# eMMC_QSPI.net
KiCad netlist of a schematic drawn in Altium Designer
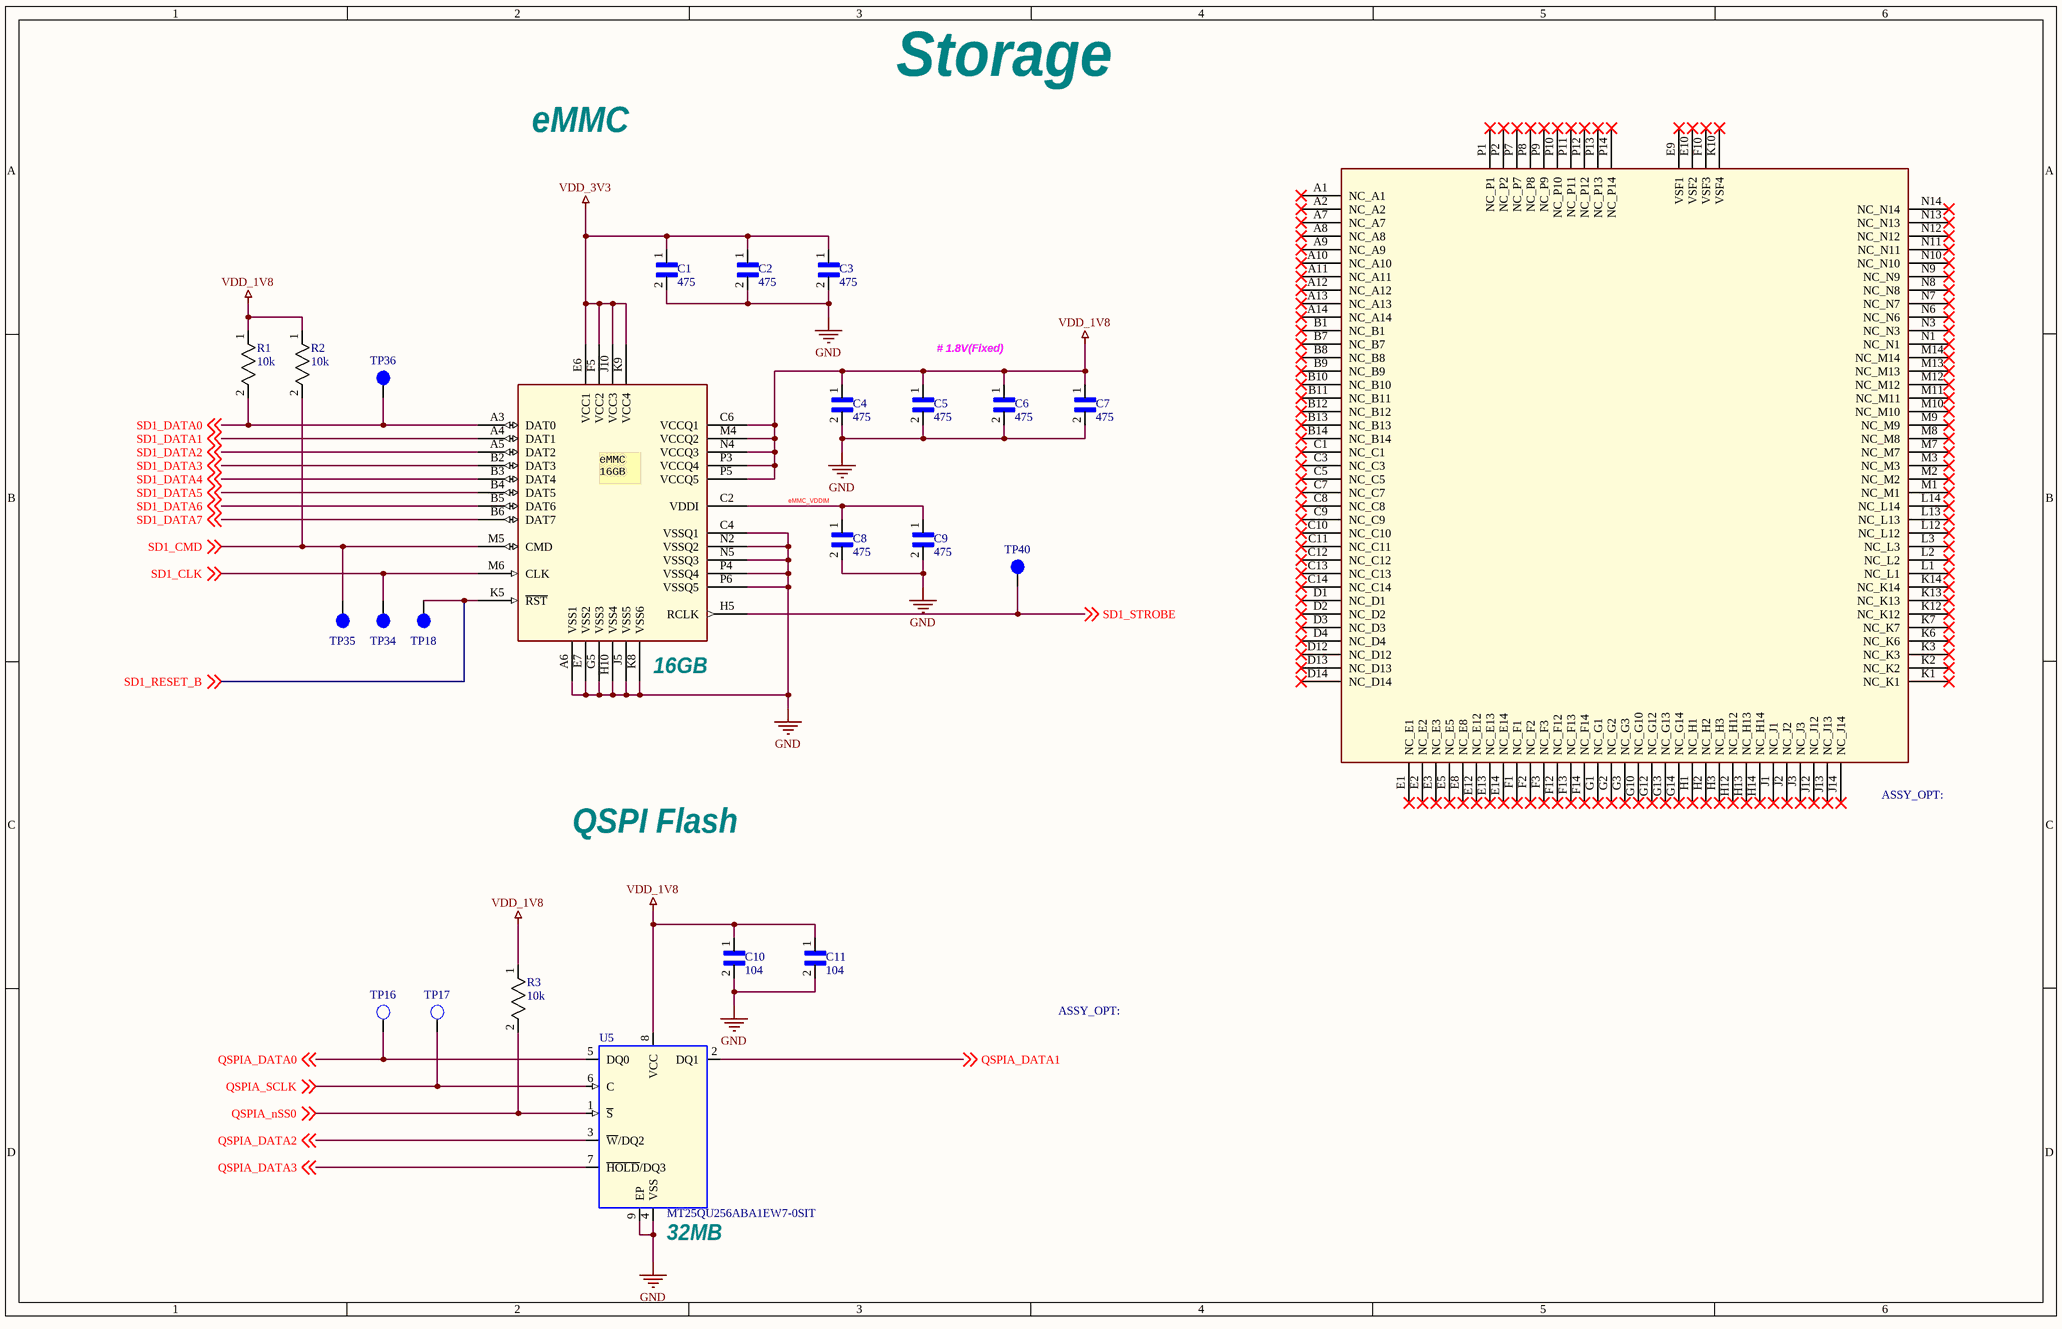
[diagram p0: eMMC_QSPI.SchDoc]

(export (version "E")
  (design (tool "Eeschema 10.0.6"))
  (components
    (comp (ref "C1")
      (value "475")
      (footprint "CAPC1005X55N2")
      (description "Multilayer Ceramic Capacitor, 4.7 uF, 50 V, ï¿½ 10%, X5R, 0402 [1005 Metric]")
      (fields
        (field (name "MANUFACTURER") "Yageo")
        (field (name "MANUFACTURER PART NUMBER") "CC0402MRX5R6BB475")
      )
      (libsource (lib "imx8mnano") (part "CC0402MRX5R6BB475"))
    )
    (comp (ref "C2")
      (value "475")
      (footprint "CAPC1005X55N2")
      (description "Multilayer Ceramic Capacitor, 4.7 uF, 50 V, ï¿½ 10%, X5R, 0402 [1005 Metric]")
      (fields
        (field (name "MANUFACTURER") "Yageo")
        (field (name "MANUFACTURER PART NUMBER") "CC0402MRX5R6BB475")
      )
      (libsource (lib "imx8mnano") (part "CC0402MRX5R6BB475"))
    )
    (comp (ref "C3")
      (value "475")
      (footprint "CAPC1005X55N2")
      (description "Multilayer Ceramic Capacitor, 4.7 uF, 50 V, ï¿½ 10%, X5R, 0402 [1005 Metric]")
      (fields
        (field (name "MANUFACTURER") "Yageo")
        (field (name "MANUFACTURER PART NUMBER") "CC0402MRX5R6BB475")
      )
      (libsource (lib "imx8mnano") (part "CC0402MRX5R6BB475"))
    )
    (comp (ref "C4")
      (value "475")
      (footprint "CAPC1005X55N2")
      (description "Multilayer Ceramic Capacitor, 4.7 uF, 50 V, ï¿½ 10%, X5R, 0402 [1005 Metric]")
      (fields
        (field (name "MANUFACTURER") "Yageo")
        (field (name "MANUFACTURER PART NUMBER") "CC0402MRX5R6BB475")
      )
      (libsource (lib "imx8mnano") (part "CC0402MRX5R6BB475"))
    )
    (comp (ref "C5")
      (value "475")
      (footprint "CAPC1005X55N2")
      (description "Multilayer Ceramic Capacitor, 4.7 uF, 50 V, ï¿½ 10%, X5R, 0402 [1005 Metric]")
      (fields
        (field (name "MANUFACTURER") "Yageo")
        (field (name "MANUFACTURER PART NUMBER") "CC0402MRX5R6BB475")
      )
      (libsource (lib "imx8mnano") (part "CC0402MRX5R6BB475"))
    )
    (comp (ref "C6")
      (value "475")
      (footprint "CAPC1005X55N2")
      (description "Multilayer Ceramic Capacitor, 4.7 uF, 50 V, ï¿½ 10%, X5R, 0402 [1005 Metric]")
      (fields
        (field (name "MANUFACTURER") "Yageo")
        (field (name "MANUFACTURER PART NUMBER") "CC0402MRX5R6BB475")
      )
      (libsource (lib "imx8mnano") (part "CC0402MRX5R6BB475"))
    )
    (comp (ref "C7")
      (value "475")
      (footprint "CAPC1005X55N2")
      (description "Multilayer Ceramic Capacitor, 4.7 uF, 50 V, ï¿½ 10%, X5R, 0402 [1005 Metric]")
      (fields
        (field (name "MANUFACTURER") "Yageo")
        (field (name "MANUFACTURER PART NUMBER") "CC0402MRX5R6BB475")
      )
      (libsource (lib "imx8mnano") (part "CC0402MRX5R6BB475"))
    )
    (comp (ref "C8")
      (value "475")
      (footprint "CAPC1005X55N2")
      (description "Multilayer Ceramic Capacitor, 4.7 uF, 50 V, ï¿½ 10%, X5R, 0402 [1005 Metric]")
      (fields
        (field (name "MANUFACTURER") "Yageo")
        (field (name "MANUFACTURER PART NUMBER") "CC0402MRX5R6BB475")
      )
      (libsource (lib "imx8mnano") (part "CC0402MRX5R6BB475"))
    )
    (comp (ref "C9")
      (value "475")
      (footprint "CAPC1005X55N2")
      (description "Multilayer Ceramic Capacitor, 4.7 uF, 50 V, ï¿½ 10%, X5R, 0402 [1005 Metric]")
      (fields
        (field (name "MANUFACTURER") "Yageo")
        (field (name "MANUFACTURER PART NUMBER") "CC0402MRX5R6BB475")
      )
      (libsource (lib "imx8mnano") (part "CC0402MRX5R6BB475"))
    )
    (comp (ref "C10")
      (value "104")
      (footprint "CAPC1005X55N2")
      (description "Multilayer Ceramic Capacitor, 0.1 uF, 16 V, ï¿½ 10%, X7R, 0402 [1005 Metric]")
      (fields
        (field (name "MANUFACTURER") "Yageo")
        (field (name "MANUFACTURER PART NUMBER") "CC0402KRX7R7BB104")
      )
      (libsource (lib "imx8mnano") (part "CC0402KRX7R7BB104"))
    )
    (comp (ref "C11")
      (value "104")
      (footprint "CAPC1005X55N2")
      (description "Multilayer Ceramic Capacitor, 0.1 uF, 16 V, ï¿½ 10%, X7R, 0402 [1005 Metric]")
      (fields
        (field (name "MANUFACTURER") "Yageo")
        (field (name "MANUFACTURER PART NUMBER") "CC0402KRX7R7BB104")
      )
      (libsource (lib "imx8mnano") (part "CC0402KRX7R7BB104"))
    )
    (comp (ref "R1")
      (value "10k")
      (footprint "RC0402X")
      (description "SMD Chip Resistor, 10 kOhm, ï¿½ 5%, 62.5 mW, 0402 [1005 Metric], Thick Film, General Purpose")
      (fields
        (field (name "MANUFACTURER") "Yageo")
        (field (name "MANUFACTURER PART NUMBER") "RC0402JR-0710KL")
      )
      (libsource (lib "imx8mnano") (part "RC0402JR-0710KL"))
    )
    (comp (ref "R2")
      (value "10k")
      (footprint "RC0402X")
      (description "SMD Chip Resistor, 10 kOhm, ï¿½ 5%, 62.5 mW, 0402 [1005 Metric], Thick Film, General Purpose")
      (fields
        (field (name "MANUFACTURER") "Yageo")
        (field (name "MANUFACTURER PART NUMBER") "RC0402JR-0710KL")
      )
      (libsource (lib "imx8mnano") (part "RC0402JR-0710KL"))
    )
    (comp (ref "R3")
      (value "10k")
      (footprint "RC0402X")
      (description "SMD Chip Resistor, 10 kOhm, ï¿½ 5%, 62.5 mW, 0402 [1005 Metric], Thick Film, General Purpose")
      (fields
        (field (name "MANUFACTURER") "Yageo")
        (field (name "MANUFACTURER PART NUMBER") "RC0402JR-0710KL")
      )
      (libsource (lib "imx8mnano") (part "RC0402JR-0710KL"))
    )
    (comp (ref "TP16")
      (value "TP_35MIL")
      (footprint "testpoint_35mil")
      (description "TEST POINT PAD .035 SMT, no part to order")
      (libsource (lib "*") (part "T POINT R"))
    )
    (comp (ref "TP17")
      (value "TP_35MIL")
      (footprint "testpoint_35mil")
      (description "TEST POINT PAD .035 SMT, no part to order")
      (libsource (lib "*") (part "T POINT R"))
    )
    (comp (ref "TP18")
      (value "tpad_020")
      (footprint "tpad_020")
      (description "TEST POINT PAD 0.5MM DIA SMT, NO PART TO ORDER")
      (libsource (lib "*") (part "TESTLOOP"))
    )
    (comp (ref "TP34")
      (value "tpad_020")
      (footprint "tpad_020")
      (description "TEST POINT PAD 0.5MM DIA SMT, NO PART TO ORDER")
      (libsource (lib "*") (part "TESTLOOP"))
    )
    (comp (ref "TP35")
      (value "TPAD_015")
      (footprint "TPAD_015")
      (description "TEST POINT PAD 15MIL DIA SMT, NO PART TO ORDER")
      (libsource (lib "*") (part "TESTLOOP"))
    )
    (comp (ref "TP36")
      (value "tpad_020")
      (footprint "tpad_020")
      (description "TEST POINT PAD 0.5MM DIA SMT, NO PART TO ORDER")
      (libsource (lib "*") (part "TESTLOOP"))
    )
    (comp (ref "TP40")
      (value "TPAD_015")
      (footprint "TPAD_015")
      (description "TEST POINT PAD 15MIL DIA SMT, NO PART TO ORDER")
      (libsource (lib "*") (part "TESTLOOP"))
    )
    (comp (ref "U1")
      (value "SDINBDG4-16G_VFBGA_153P")
      (footprint "BGA153N50P14X14_1300X1150X80")
      (libsource (lib "imx8mnano") (part "SDINBDG4-16G_VFBGA_153P"))
    )
    (comp (ref "U5")
      (value "MT25QU256ABA1EW7-0SIT")
      (footprint "dfn8_1p27_6x5mm_3p1")
      (description "IC MEM FLASH SERIAL NOR 256MBIT 166MHZ 1.7-2V WPDFN8")
      (fields (field (name "VOLTAGE") "1.7-2V"))
      (libsource (lib "*") (part "MT25QL256ABA1EW9_9P"))
    )
  )
  (nets
    (net (code "1") (name "/eMMC_VDDIM") (class "Default")
      (node (ref "C8") (pin "1") (pinfunction "1_1") (pintype "passive"))
      (node (ref "C9") (pin "1") (pinfunction "1_1") (pintype "passive"))
      (node (ref "U1") (pin "C2") (pinfunction "VDDI_C2") (pintype "power_in"))
    )
    (net (code "2") (name "GND") (class "Default")
      (node (ref "C1") (pin "2") (pinfunction "2_2") (pintype "passive"))
      (node (ref "C10") (pin "2") (pinfunction "2_2") (pintype "passive"))
      (node (ref "C11") (pin "2") (pinfunction "2_2") (pintype "passive"))
      (node (ref "C2") (pin "2") (pinfunction "2_2") (pintype "passive"))
      (node (ref "C3") (pin "2") (pinfunction "2_2") (pintype "passive"))
      (node (ref "C4") (pin "2") (pinfunction "2_2") (pintype "passive"))
      (node (ref "C5") (pin "2") (pinfunction "2_2") (pintype "passive"))
      (node (ref "C6") (pin "2") (pinfunction "2_2") (pintype "passive"))
      (node (ref "C7") (pin "2") (pinfunction "2_2") (pintype "passive"))
      (node (ref "C8") (pin "2") (pinfunction "2_2") (pintype "passive"))
      (node (ref "C9") (pin "2") (pinfunction "2_2") (pintype "passive"))
      (node (ref "U1") (pin "A6") (pinfunction "VSS1_A6") (pintype "power_in"))
      (node (ref "U1") (pin "C4") (pinfunction "VSSQ1_C4") (pintype "power_in"))
      (node (ref "U1") (pin "E7") (pinfunction "VSS2_E7") (pintype "power_in"))
      (node (ref "U1") (pin "G5") (pinfunction "VSS3_G5") (pintype "power_in"))
      (node (ref "U1") (pin "H10") (pinfunction "VSS4_H10") (pintype "power_in"))
      (node (ref "U1") (pin "J5") (pinfunction "VSS5_J5") (pintype "power_in"))
      (node (ref "U1") (pin "K8") (pinfunction "VSS6_K8") (pintype "power_in"))
      (node (ref "U1") (pin "N2") (pinfunction "VSSQ2_N2") (pintype "power_in"))
      (node (ref "U1") (pin "N5") (pinfunction "VSSQ3_N5") (pintype "power_in"))
      (node (ref "U1") (pin "P4") (pinfunction "VSSQ4_P4") (pintype "power_in"))
      (node (ref "U1") (pin "P6") (pinfunction "VSSQ5_P6") (pintype "power_in"))
      (node (ref "U5") (pin "4") (pinfunction "VSS_4") (pintype "power_in"))
      (node (ref "U5") (pin "9") (pinfunction "EP_9") (pintype "power_in"))
    )
    (net (code "3") (name "QSPIA_DATA0") (class "Default")
      (node (ref "TP16") (pin "1") (pinfunction "TP_1") (pintype "passive"))
      (node (ref "U5") (pin "5") (pinfunction "DQ0_5") (pintype "bidirectional"))
    )
    (net (code "4") (name "QSPIA_DATA1") (class "Default")
      (node (ref "U5") (pin "2") (pinfunction "DQ1_2") (pintype "bidirectional"))
    )
    (net (code "5") (name "QSPIA_DATA2") (class "Default")
      (node (ref "U5") (pin "3") (pinfunction "~{W}/DQ2_3") (pintype "bidirectional"))
    )
    (net (code "6") (name "QSPIA_DATA3") (class "Default")
      (node (ref "U5") (pin "7") (pinfunction "~{HOLD}/DQ3_7") (pintype "bidirectional"))
    )
    (net (code "7") (name "QSPIA_SCLK") (class "Default")
      (node (ref "TP17") (pin "1") (pinfunction "TP_1") (pintype "passive"))
      (node (ref "U5") (pin "6") (pinfunction "C_6") (pintype "input"))
    )
    (net (code "8") (name "QSPIA_nSS0") (class "Default")
      (node (ref "R3") (pin "2") (pinfunction "2_2") (pintype "passive"))
      (node (ref "U5") (pin "1") (pinfunction "~{S}_1") (pintype "input"))
    )
    (net (code "9") (name "SD1_CLK") (class "Default")
      (node (ref "TP34") (pin "1") (pinfunction "Pin1_1") (pintype "passive"))
      (node (ref "U1") (pin "M6") (pinfunction "CLK_M6") (pintype "input"))
    )
    (net (code "10") (name "SD1_CMD") (class "Default")
      (node (ref "R2") (pin "2") (pinfunction "2_2") (pintype "passive"))
      (node (ref "TP35") (pin "1") (pinfunction "Pin1_1") (pintype "passive"))
      (node (ref "U1") (pin "M5") (pinfunction "CMD_M5") (pintype "bidirectional"))
    )
    (net (code "11") (name "SD1_DATA0") (class "Default")
      (node (ref "R1") (pin "2") (pinfunction "2_2") (pintype "passive"))
      (node (ref "TP36") (pin "1") (pinfunction "Pin1_1") (pintype "passive"))
      (node (ref "U1") (pin "A3") (pinfunction "DAT0_A3") (pintype "bidirectional"))
    )
    (net (code "12") (name "SD1_DATA1") (class "Default")
      (node (ref "U1") (pin "A4") (pinfunction "DAT1_A4") (pintype "bidirectional"))
    )
    (net (code "13") (name "SD1_DATA2") (class "Default")
      (node (ref "U1") (pin "A5") (pinfunction "DAT2_A5") (pintype "bidirectional"))
    )
    (net (code "14") (name "SD1_DATA3") (class "Default")
      (node (ref "U1") (pin "B2") (pinfunction "DAT3_B2") (pintype "bidirectional"))
    )
    (net (code "15") (name "SD1_DATA4") (class "Default")
      (node (ref "U1") (pin "B3") (pinfunction "DAT4_B3") (pintype "bidirectional"))
    )
    (net (code "16") (name "SD1_DATA5") (class "Default")
      (node (ref "U1") (pin "B4") (pinfunction "DAT5_B4") (pintype "bidirectional"))
    )
    (net (code "17") (name "SD1_DATA6") (class "Default")
      (node (ref "U1") (pin "B5") (pinfunction "DAT6_B5") (pintype "bidirectional"))
    )
    (net (code "18") (name "SD1_DATA7") (class "Default")
      (node (ref "U1") (pin "B6") (pinfunction "DAT7_B6") (pintype "bidirectional"))
    )
    (net (code "19") (name "SD1_RESET_B") (class "Default")
      (node (ref "TP18") (pin "1") (pinfunction "Pin1_1") (pintype "passive"))
      (node (ref "U1") (pin "K5") (pinfunction "~{RST}_K5") (pintype "input"))
    )
    (net (code "20") (name "SD1_STROBE") (class "Default")
      (node (ref "TP40") (pin "1") (pinfunction "Pin1_1") (pintype "passive"))
      (node (ref "U1") (pin "H5") (pinfunction "RCLK_H5") (pintype "output"))
    )
    (net (code "21") (name "VDD_1V8") (class "Default")
      (node (ref "C10") (pin "1") (pinfunction "1_1") (pintype "passive"))
      (node (ref "C11") (pin "1") (pinfunction "1_1") (pintype "passive"))
      (node (ref "C4") (pin "1") (pinfunction "1_1") (pintype "passive"))
      (node (ref "C5") (pin "1") (pinfunction "1_1") (pintype "passive"))
      (node (ref "C6") (pin "1") (pinfunction "1_1") (pintype "passive"))
      (node (ref "C7") (pin "1") (pinfunction "1_1") (pintype "passive"))
      (node (ref "R1") (pin "1") (pinfunction "1_1") (pintype "passive"))
      (node (ref "R2") (pin "1") (pinfunction "1_1") (pintype "passive"))
      (node (ref "R3") (pin "1") (pinfunction "1_1") (pintype "passive"))
      (node (ref "U1") (pin "C6") (pinfunction "VCCQ1_C6") (pintype "power_in"))
      (node (ref "U1") (pin "M4") (pinfunction "VCCQ2_M4") (pintype "power_in"))
      (node (ref "U1") (pin "N4") (pinfunction "VCCQ3_N4") (pintype "power_in"))
      (node (ref "U1") (pin "P3") (pinfunction "VCCQ4_P3") (pintype "power_in"))
      (node (ref "U1") (pin "P5") (pinfunction "VCCQ5_P5") (pintype "power_in"))
      (node (ref "U5") (pin "8") (pinfunction "VCC_8") (pintype "power_in"))
    )
    (net (code "22") (name "VDD_3V3") (class "Default")
      (node (ref "C1") (pin "1") (pinfunction "1_1") (pintype "passive"))
      (node (ref "C2") (pin "1") (pinfunction "1_1") (pintype "passive"))
      (node (ref "C3") (pin "1") (pinfunction "1_1") (pintype "passive"))
      (node (ref "U1") (pin "E6") (pinfunction "VCC1_E6") (pintype "power_in"))
      (node (ref "U1") (pin "F5") (pinfunction "VCC2_F5") (pintype "power_in"))
      (node (ref "U1") (pin "J10") (pinfunction "VCC3_J10") (pintype "power_in"))
      (node (ref "U1") (pin "K9") (pinfunction "VCC4_K9") (pintype "power_in"))
    )
    (net (code "23") (name "unconnected-(U1B-NC_A1-PadA1)") (class "Default")
      (node (ref "U1") (pin "A1") (pinfunction "NC_A1_A1") (pintype "passive+no_connect"))
    )
    (net (code "24") (name "unconnected-(U1B-NC_A2-PadA2)") (class "Default")
      (node (ref "U1") (pin "A2") (pinfunction "NC_A2_A2") (pintype "passive+no_connect"))
    )
    (net (code "25") (name "unconnected-(U1B-NC_A7-PadA7)") (class "Default")
      (node (ref "U1") (pin "A7") (pinfunction "NC_A7_A7") (pintype "passive+no_connect"))
    )
    (net (code "26") (name "unconnected-(U1B-NC_A8-PadA8)") (class "Default")
      (node (ref "U1") (pin "A8") (pinfunction "NC_A8_A8") (pintype "passive+no_connect"))
    )
    (net (code "27") (name "unconnected-(U1B-NC_A9-PadA9)") (class "Default")
      (node (ref "U1") (pin "A9") (pinfunction "NC_A9_A9") (pintype "passive+no_connect"))
    )
    (net (code "28") (name "unconnected-(U1B-NC_A10-PadA10)") (class "Default")
      (node (ref "U1") (pin "A10") (pinfunction "NC_A10_A10") (pintype "passive+no_connect"))
    )
    (net (code "29") (name "unconnected-(U1B-NC_A11-PadA11)") (class "Default")
      (node (ref "U1") (pin "A11") (pinfunction "NC_A11_A11") (pintype "passive+no_connect"))
    )
    (net (code "30") (name "unconnected-(U1B-NC_A12-PadA12)") (class "Default")
      (node (ref "U1") (pin "A12") (pinfunction "NC_A12_A12") (pintype "passive+no_connect"))
    )
    (net (code "31") (name "unconnected-(U1B-NC_A13-PadA13)") (class "Default")
      (node (ref "U1") (pin "A13") (pinfunction "NC_A13_A13") (pintype "passive+no_connect"))
    )
    (net (code "32") (name "unconnected-(U1B-NC_A14-PadA14)") (class "Default")
      (node (ref "U1") (pin "A14") (pinfunction "NC_A14_A14") (pintype "passive+no_connect"))
    )
    (net (code "33") (name "unconnected-(U1B-NC_B1-PadB1)") (class "Default")
      (node (ref "U1") (pin "B1") (pinfunction "NC_B1_B1") (pintype "passive+no_connect"))
    )
    (net (code "34") (name "unconnected-(U1B-NC_B7-PadB7)") (class "Default")
      (node (ref "U1") (pin "B7") (pinfunction "NC_B7_B7") (pintype "passive+no_connect"))
    )
    (net (code "35") (name "unconnected-(U1B-NC_B8-PadB8)") (class "Default")
      (node (ref "U1") (pin "B8") (pinfunction "NC_B8_B8") (pintype "passive+no_connect"))
    )
    (net (code "36") (name "unconnected-(U1B-NC_B9-PadB9)") (class "Default")
      (node (ref "U1") (pin "B9") (pinfunction "NC_B9_B9") (pintype "passive+no_connect"))
    )
    (net (code "37") (name "unconnected-(U1B-NC_B10-PadB10)") (class "Default")
      (node (ref "U1") (pin "B10") (pinfunction "NC_B10_B10") (pintype "passive+no_connect"))
    )
    (net (code "38") (name "unconnected-(U1B-NC_B11-PadB11)") (class "Default")
      (node (ref "U1") (pin "B11") (pinfunction "NC_B11_B11") (pintype "passive+no_connect"))
    )
    (net (code "39") (name "unconnected-(U1B-NC_B12-PadB12)") (class "Default")
      (node (ref "U1") (pin "B12") (pinfunction "NC_B12_B12") (pintype "passive+no_connect"))
    )
    (net (code "40") (name "unconnected-(U1B-NC_B13-PadB13)") (class "Default")
      (node (ref "U1") (pin "B13") (pinfunction "NC_B13_B13") (pintype "passive+no_connect"))
    )
    (net (code "41") (name "unconnected-(U1B-NC_B14-PadB14)") (class "Default")
      (node (ref "U1") (pin "B14") (pinfunction "NC_B14_B14") (pintype "passive+no_connect"))
    )
    (net (code "42") (name "unconnected-(U1B-NC_C1-PadC1)") (class "Default")
      (node (ref "U1") (pin "C1") (pinfunction "NC_C1_C1") (pintype "passive+no_connect"))
    )
    (net (code "43") (name "unconnected-(U1B-NC_C3-PadC3)") (class "Default")
      (node (ref "U1") (pin "C3") (pinfunction "NC_C3_C3") (pintype "passive+no_connect"))
    )
    (net (code "44") (name "unconnected-(U1B-NC_C5-PadC5)") (class "Default")
      (node (ref "U1") (pin "C5") (pinfunction "NC_C5_C5") (pintype "passive+no_connect"))
    )
    (net (code "45") (name "unconnected-(U1B-NC_C7-PadC7)") (class "Default")
      (node (ref "U1") (pin "C7") (pinfunction "NC_C7_C7") (pintype "passive+no_connect"))
    )
    (net (code "46") (name "unconnected-(U1B-NC_C8-PadC8)") (class "Default")
      (node (ref "U1") (pin "C8") (pinfunction "NC_C8_C8") (pintype "passive+no_connect"))
    )
    (net (code "47") (name "unconnected-(U1B-NC_C9-PadC9)") (class "Default")
      (node (ref "U1") (pin "C9") (pinfunction "NC_C9_C9") (pintype "passive+no_connect"))
    )
    (net (code "48") (name "unconnected-(U1B-NC_C10-PadC10)") (class "Default")
      (node (ref "U1") (pin "C10") (pinfunction "NC_C10_C10") (pintype "passive+no_connect"))
    )
    (net (code "49") (name "unconnected-(U1B-NC_C11-PadC11)") (class "Default")
      (node (ref "U1") (pin "C11") (pinfunction "NC_C11_C11") (pintype "passive+no_connect"))
    )
    (net (code "50") (name "unconnected-(U1B-NC_C12-PadC12)") (class "Default")
      (node (ref "U1") (pin "C12") (pinfunction "NC_C12_C12") (pintype "passive+no_connect"))
    )
    (net (code "51") (name "unconnected-(U1B-NC_C13-PadC13)") (class "Default")
      (node (ref "U1") (pin "C13") (pinfunction "NC_C13_C13") (pintype "passive+no_connect"))
    )
    (net (code "52") (name "unconnected-(U1B-NC_C14-PadC14)") (class "Default")
      (node (ref "U1") (pin "C14") (pinfunction "NC_C14_C14") (pintype "passive+no_connect"))
    )
    (net (code "53") (name "unconnected-(U1B-NC_D1-PadD1)") (class "Default")
      (node (ref "U1") (pin "D1") (pinfunction "NC_D1_D1") (pintype "passive+no_connect"))
    )
    (net (code "54") (name "unconnected-(U1B-NC_D2-PadD2)") (class "Default")
      (node (ref "U1") (pin "D2") (pinfunction "NC_D2_D2") (pintype "passive+no_connect"))
    )
    (net (code "55") (name "unconnected-(U1B-NC_D3-PadD3)") (class "Default")
      (node (ref "U1") (pin "D3") (pinfunction "NC_D3_D3") (pintype "passive+no_connect"))
    )
    (net (code "56") (name "unconnected-(U1B-NC_D4-PadD4)") (class "Default")
      (node (ref "U1") (pin "D4") (pinfunction "NC_D4_D4") (pintype "passive+no_connect"))
    )
    (net (code "57") (name "unconnected-(U1B-NC_D12-PadD12)") (class "Default")
      (node (ref "U1") (pin "D12") (pinfunction "NC_D12_D12") (pintype "passive+no_connect"))
    )
    (net (code "58") (name "unconnected-(U1B-NC_D13-PadD13)") (class "Default")
      (node (ref "U1") (pin "D13") (pinfunction "NC_D13_D13") (pintype "passive+no_connect"))
    )
    (net (code "59") (name "unconnected-(U1B-NC_D14-PadD14)") (class "Default")
      (node (ref "U1") (pin "D14") (pinfunction "NC_D14_D14") (pintype "passive+no_connect"))
    )
    (net (code "60") (name "unconnected-(U1B-NC_E1-PadE1)") (class "Default")
      (node (ref "U1") (pin "E1") (pinfunction "NC_E1_E1") (pintype "passive+no_connect"))
    )
    (net (code "61") (name "unconnected-(U1B-NC_E2-PadE2)") (class "Default")
      (node (ref "U1") (pin "E2") (pinfunction "NC_E2_E2") (pintype "passive+no_connect"))
    )
    (net (code "62") (name "unconnected-(U1B-NC_E3-PadE3)") (class "Default")
      (node (ref "U1") (pin "E3") (pinfunction "NC_E3_E3") (pintype "passive+no_connect"))
    )
    (net (code "63") (name "unconnected-(U1B-NC_E5-PadE5)") (class "Default")
      (node (ref "U1") (pin "E5") (pinfunction "NC_E5_E5") (pintype "passive+no_connect"))
    )
    (net (code "64") (name "unconnected-(U1B-NC_E8-PadE8)") (class "Default")
      (node (ref "U1") (pin "E8") (pinfunction "NC_E8_E8") (pintype "passive+no_connect"))
    )
    (net (code "65") (name "unconnected-(U1B-NC_E12-PadE12)") (class "Default")
      (node (ref "U1") (pin "E12") (pinfunction "NC_E12_E12") (pintype "passive+no_connect"))
    )
    (net (code "66") (name "unconnected-(U1B-NC_E13-PadE13)") (class "Default")
      (node (ref "U1") (pin "E13") (pinfunction "NC_E13_E13") (pintype "passive+no_connect"))
    )
    (net (code "67") (name "unconnected-(U1B-NC_E14-PadE14)") (class "Default")
      (node (ref "U1") (pin "E14") (pinfunction "NC_E14_E14") (pintype "passive+no_connect"))
    )
    (net (code "68") (name "unconnected-(U1B-NC_F1-PadF1)") (class "Default")
      (node (ref "U1") (pin "F1") (pinfunction "NC_F1_F1") (pintype "passive+no_connect"))
    )
    (net (code "69") (name "unconnected-(U1B-NC_F2-PadF2)") (class "Default")
      (node (ref "U1") (pin "F2") (pinfunction "NC_F2_F2") (pintype "passive+no_connect"))
    )
    (net (code "70") (name "unconnected-(U1B-NC_F3-PadF3)") (class "Default")
      (node (ref "U1") (pin "F3") (pinfunction "NC_F3_F3") (pintype "passive+no_connect"))
    )
    (net (code "71") (name "unconnected-(U1B-NC_F12-PadF12)") (class "Default")
      (node (ref "U1") (pin "F12") (pinfunction "NC_F12_F12") (pintype "passive+no_connect"))
    )
    (net (code "72") (name "unconnected-(U1B-NC_F13-PadF13)") (class "Default")
      (node (ref "U1") (pin "F13") (pinfunction "NC_F13_F13") (pintype "passive+no_connect"))
    )
    (net (code "73") (name "unconnected-(U1B-NC_F14-PadF14)") (class "Default")
      (node (ref "U1") (pin "F14") (pinfunction "NC_F14_F14") (pintype "passive+no_connect"))
    )
    (net (code "74") (name "unconnected-(U1B-NC_G1-PadG1)") (class "Default")
      (node (ref "U1") (pin "G1") (pinfunction "NC_G1_G1") (pintype "passive+no_connect"))
    )
    (net (code "75") (name "unconnected-(U1B-NC_G2-PadG2)") (class "Default")
      (node (ref "U1") (pin "G2") (pinfunction "NC_G2_G2") (pintype "passive+no_connect"))
    )
    (net (code "76") (name "unconnected-(U1B-NC_G3-PadG3)") (class "Default")
      (node (ref "U1") (pin "G3") (pinfunction "NC_G3_G3") (pintype "passive+no_connect"))
    )
    (net (code "77") (name "unconnected-(U1B-NC_G10-PadG10)") (class "Default")
      (node (ref "U1") (pin "G10") (pinfunction "NC_G10_G10") (pintype "passive+no_connect"))
    )
    (net (code "78") (name "unconnected-(U1B-NC_G12-PadG12)") (class "Default")
      (node (ref "U1") (pin "G12") (pinfunction "NC_G12_G12") (pintype "passive+no_connect"))
    )
    (net (code "79") (name "unconnected-(U1B-NC_G13-PadG13)") (class "Default")
      (node (ref "U1") (pin "G13") (pinfunction "NC_G13_G13") (pintype "passive+no_connect"))
    )
    (net (code "80") (name "unconnected-(U1B-NC_G14-PadG14)") (class "Default")
      (node (ref "U1") (pin "G14") (pinfunction "NC_G14_G14") (pintype "passive+no_connect"))
    )
    (net (code "81") (name "unconnected-(U1B-NC_H1-PadH1)") (class "Default")
      (node (ref "U1") (pin "H1") (pinfunction "NC_H1_H1") (pintype "passive+no_connect"))
    )
    (net (code "82") (name "unconnected-(U1B-NC_H2-PadH2)") (class "Default")
      (node (ref "U1") (pin "H2") (pinfunction "NC_H2_H2") (pintype "passive+no_connect"))
    )
    (net (code "83") (name "unconnected-(U1B-NC_H3-PadH3)") (class "Default")
      (node (ref "U1") (pin "H3") (pinfunction "NC_H3_H3") (pintype "passive+no_connect"))
    )
    (net (code "84") (name "unconnected-(U1B-NC_H12-PadH12)") (class "Default")
      (node (ref "U1") (pin "H12") (pinfunction "NC_H12_H12") (pintype "passive+no_connect"))
    )
    (net (code "85") (name "unconnected-(U1B-NC_H13-PadH13)") (class "Default")
      (node (ref "U1") (pin "H13") (pinfunction "NC_H13_H13") (pintype "passive+no_connect"))
    )
    (net (code "86") (name "unconnected-(U1B-NC_H14-PadH14)") (class "Default")
      (node (ref "U1") (pin "H14") (pinfunction "NC_H14_H14") (pintype "passive+no_connect"))
    )
    (net (code "87") (name "unconnected-(U1B-NC_J1-PadJ1)") (class "Default")
      (node (ref "U1") (pin "J1") (pinfunction "NC_J1_J1") (pintype "passive+no_connect"))
    )
    (net (code "88") (name "unconnected-(U1B-NC_J2-PadJ2)") (class "Default")
      (node (ref "U1") (pin "J2") (pinfunction "NC_J2_J2") (pintype "passive+no_connect"))
    )
    (net (code "89") (name "unconnected-(U1B-NC_J3-PadJ3)") (class "Default")
      (node (ref "U1") (pin "J3") (pinfunction "NC_J3_J3") (pintype "passive+no_connect"))
    )
    (net (code "90") (name "unconnected-(U1B-NC_J12-PadJ12)") (class "Default")
      (node (ref "U1") (pin "J12") (pinfunction "NC_J12_J12") (pintype "passive+no_connect"))
    )
    (net (code "91") (name "unconnected-(U1B-NC_J13-PadJ13)") (class "Default")
      (node (ref "U1") (pin "J13") (pinfunction "NC_J13_J13") (pintype "passive+no_connect"))
    )
    (net (code "92") (name "unconnected-(U1B-NC_J14-PadJ14)") (class "Default")
      (node (ref "U1") (pin "J14") (pinfunction "NC_J14_J14") (pintype "passive+no_connect"))
    )
    (net (code "93") (name "unconnected-(U1B-NC_K1-PadK1)") (class "Default")
      (node (ref "U1") (pin "K1") (pinfunction "NC_K1_K1") (pintype "passive+no_connect"))
    )
    (net (code "94") (name "unconnected-(U1B-NC_K2-PadK2)") (class "Default")
      (node (ref "U1") (pin "K2") (pinfunction "NC_K2_K2") (pintype "passive+no_connect"))
    )
    (net (code "95") (name "unconnected-(U1B-NC_K3-PadK3)") (class "Default")
      (node (ref "U1") (pin "K3") (pinfunction "NC_K3_K3") (pintype "passive+no_connect"))
    )
    (net (code "96") (name "unconnected-(U1B-NC_K6-PadK6)") (class "Default")
      (node (ref "U1") (pin "K6") (pinfunction "NC_K6_K6") (pintype "passive+no_connect"))
    )
    (net (code "97") (name "unconnected-(U1B-NC_K7-PadK7)") (class "Default")
      (node (ref "U1") (pin "K7") (pinfunction "NC_K7_K7") (pintype "passive+no_connect"))
    )
    (net (code "98") (name "unconnected-(U1B-NC_K12-PadK12)") (class "Default")
      (node (ref "U1") (pin "K12") (pinfunction "NC_K12_K12") (pintype "passive+no_connect"))
    )
    (net (code "99") (name "unconnected-(U1B-NC_K13-PadK13)") (class "Default")
      (node (ref "U1") (pin "K13") (pinfunction "NC_K13_K13") (pintype "passive+no_connect"))
    )
    (net (code "100") (name "unconnected-(U1B-NC_K14-PadK14)") (class "Default")
      (node (ref "U1") (pin "K14") (pinfunction "NC_K14_K14") (pintype "passive+no_connect"))
    )
    (net (code "101") (name "unconnected-(U1B-NC_L1-PadL1)") (class "Default")
      (node (ref "U1") (pin "L1") (pinfunction "NC_L1_L1") (pintype "passive+no_connect"))
    )
    (net (code "102") (name "unconnected-(U1B-NC_L2-PadL2)") (class "Default")
      (node (ref "U1") (pin "L2") (pinfunction "NC_L2_L2") (pintype "passive+no_connect"))
    )
    (net (code "103") (name "unconnected-(U1B-NC_L3-PadL3)") (class "Default")
      (node (ref "U1") (pin "L3") (pinfunction "NC_L3_L3") (pintype "passive+no_connect"))
    )
    (net (code "104") (name "unconnected-(U1B-NC_L12-PadL12)") (class "Default")
      (node (ref "U1") (pin "L12") (pinfunction "NC_L12_L12") (pintype "passive+no_connect"))
    )
    (net (code "105") (name "unconnected-(U1B-NC_L13-PadL13)") (class "Default")
      (node (ref "U1") (pin "L13") (pinfunction "NC_L13_L13") (pintype "passive+no_connect"))
    )
    (net (code "106") (name "unconnected-(U1B-NC_L14-PadL14)") (class "Default")
      (node (ref "U1") (pin "L14") (pinfunction "NC_L14_L14") (pintype "passive+no_connect"))
    )
    (net (code "107") (name "unconnected-(U1B-NC_M1-PadM1)") (class "Default")
      (node (ref "U1") (pin "M1") (pinfunction "NC_M1_M1") (pintype "passive+no_connect"))
    )
    (net (code "108") (name "unconnected-(U1B-NC_M2-PadM2)") (class "Default")
      (node (ref "U1") (pin "M2") (pinfunction "NC_M2_M2") (pintype "passive+no_connect"))
    )
    (net (code "109") (name "unconnected-(U1B-NC_M3-PadM3)") (class "Default")
      (node (ref "U1") (pin "M3") (pinfunction "NC_M3_M3") (pintype "passive+no_connect"))
    )
    (net (code "110") (name "unconnected-(U1B-NC_M7-PadM7)") (class "Default")
      (node (ref "U1") (pin "M7") (pinfunction "NC_M7_M7") (pintype "passive+no_connect"))
    )
    (net (code "111") (name "unconnected-(U1B-NC_M8-PadM8)") (class "Default")
      (node (ref "U1") (pin "M8") (pinfunction "NC_M8_M8") (pintype "passive+no_connect"))
    )
    (net (code "112") (name "unconnected-(U1B-NC_M9-PadM9)") (class "Default")
      (node (ref "U1") (pin "M9") (pinfunction "NC_M9_M9") (pintype "passive+no_connect"))
    )
    (net (code "113") (name "unconnected-(U1B-NC_M10-PadM10)") (class "Default")
      (node (ref "U1") (pin "M10") (pinfunction "NC_M10_M10") (pintype "passive+no_connect"))
    )
    (net (code "114") (name "unconnected-(U1B-NC_M11-PadM11)") (class "Default")
      (node (ref "U1") (pin "M11") (pinfunction "NC_M11_M11") (pintype "passive+no_connect"))
    )
    (net (code "115") (name "unconnected-(U1B-NC_M12-PadM12)") (class "Default")
      (node (ref "U1") (pin "M12") (pinfunction "NC_M12_M12") (pintype "passive+no_connect"))
    )
    (net (code "116") (name "unconnected-(U1B-NC_M13-PadM13)") (class "Default")
      (node (ref "U1") (pin "M13") (pinfunction "NC_M13_M13") (pintype "passive+no_connect"))
    )
    (net (code "117") (name "unconnected-(U1B-NC_M14-PadM14)") (class "Default")
      (node (ref "U1") (pin "M14") (pinfunction "NC_M14_M14") (pintype "passive+no_connect"))
    )
    (net (code "118") (name "unconnected-(U1B-NC_N1-PadN1)") (class "Default")
      (node (ref "U1") (pin "N1") (pinfunction "NC_N1_N1") (pintype "passive+no_connect"))
    )
    (net (code "119") (name "unconnected-(U1B-NC_N3-PadN3)") (class "Default")
      (node (ref "U1") (pin "N3") (pinfunction "NC_N3_N3") (pintype "passive+no_connect"))
    )
    (net (code "120") (name "unconnected-(U1B-NC_N6-PadN6)") (class "Default")
      (node (ref "U1") (pin "N6") (pinfunction "NC_N6_N6") (pintype "passive+no_connect"))
    )
    (net (code "121") (name "unconnected-(U1B-NC_N7-PadN7)") (class "Default")
      (node (ref "U1") (pin "N7") (pinfunction "NC_N7_N7") (pintype "passive+no_connect"))
    )
    (net (code "122") (name "unconnected-(U1B-NC_N8-PadN8)") (class "Default")
      (node (ref "U1") (pin "N8") (pinfunction "NC_N8_N8") (pintype "passive+no_connect"))
    )
    (net (code "123") (name "unconnected-(U1B-NC_N9-PadN9)") (class "Default")
      (node (ref "U1") (pin "N9") (pinfunction "NC_N9_N9") (pintype "passive+no_connect"))
    )
    (net (code "124") (name "unconnected-(U1B-NC_N10-PadN10)") (class "Default")
      (node (ref "U1") (pin "N10") (pinfunction "NC_N10_N10") (pintype "passive+no_connect"))
    )
    (net (code "125") (name "unconnected-(U1B-NC_N11-PadN11)") (class "Default")
      (node (ref "U1") (pin "N11") (pinfunction "NC_N11_N11") (pintype "passive+no_connect"))
    )
    (net (code "126") (name "unconnected-(U1B-NC_N12-PadN12)") (class "Default")
      (node (ref "U1") (pin "N12") (pinfunction "NC_N12_N12") (pintype "passive+no_connect"))
    )
    (net (code "127") (name "unconnected-(U1B-NC_N13-PadN13)") (class "Default")
      (node (ref "U1") (pin "N13") (pinfunction "NC_N13_N13") (pintype "passive+no_connect"))
    )
    (net (code "128") (name "unconnected-(U1B-NC_N14-PadN14)") (class "Default")
      (node (ref "U1") (pin "N14") (pinfunction "NC_N14_N14") (pintype "passive+no_connect"))
    )
    (net (code "129") (name "unconnected-(U1B-NC_P1-PadP1)") (class "Default")
      (node (ref "U1") (pin "P1") (pinfunction "NC_P1_P1") (pintype "passive+no_connect"))
    )
    (net (code "130") (name "unconnected-(U1B-NC_P2-PadP2)") (class "Default")
      (node (ref "U1") (pin "P2") (pinfunction "NC_P2_P2") (pintype "passive+no_connect"))
    )
    (net (code "131") (name "unconnected-(U1B-NC_P7-PadP7)") (class "Default")
      (node (ref "U1") (pin "P7") (pinfunction "NC_P7_P7") (pintype "passive+no_connect"))
    )
    (net (code "132") (name "unconnected-(U1B-NC_P8-PadP8)") (class "Default")
      (node (ref "U1") (pin "P8") (pinfunction "NC_P8_P8") (pintype "passive+no_connect"))
    )
    (net (code "133") (name "unconnected-(U1B-NC_P9-PadP9)") (class "Default")
      (node (ref "U1") (pin "P9") (pinfunction "NC_P9_P9") (pintype "passive+no_connect"))
    )
    (net (code "134") (name "unconnected-(U1B-NC_P10-PadP10)") (class "Default")
      (node (ref "U1") (pin "P10") (pinfunction "NC_P10_P10") (pintype "passive+no_connect"))
    )
    (net (code "135") (name "unconnected-(U1B-NC_P11-PadP11)") (class "Default")
      (node (ref "U1") (pin "P11") (pinfunction "NC_P11_P11") (pintype "passive+no_connect"))
    )
    (net (code "136") (name "unconnected-(U1B-NC_P12-PadP12)") (class "Default")
      (node (ref "U1") (pin "P12") (pinfunction "NC_P12_P12") (pintype "passive+no_connect"))
    )
    (net (code "137") (name "unconnected-(U1B-NC_P13-PadP13)") (class "Default")
      (node (ref "U1") (pin "P13") (pinfunction "NC_P13_P13") (pintype "passive+no_connect"))
    )
    (net (code "138") (name "unconnected-(U1B-NC_P14-PadP14)") (class "Default")
      (node (ref "U1") (pin "P14") (pinfunction "NC_P14_P14") (pintype "passive+no_connect"))
    )
    (net (code "139") (name "unconnected-(U1B-VSF1-PadE9)") (class "Default")
      (node (ref "U1") (pin "E9") (pinfunction "VSF1_E9") (pintype "passive+no_connect"))
    )
    (net (code "140") (name "unconnected-(U1B-VSF2-PadE10)") (class "Default")
      (node (ref "U1") (pin "E10") (pinfunction "VSF2_E10") (pintype "passive+no_connect"))
    )
    (net (code "141") (name "unconnected-(U1B-VSF3-PadF10)") (class "Default")
      (node (ref "U1") (pin "F10") (pinfunction "VSF3_F10") (pintype "passive+no_connect"))
    )
    (net (code "142") (name "unconnected-(U1B-VSF4-PadK10)") (class "Default")
      (node (ref "U1") (pin "K10") (pinfunction "VSF4_K10") (pintype "passive+no_connect"))
    )
  )
)
